# ultra_wideband.net
KiCad netlist of a schematic drawn in Altium Designer
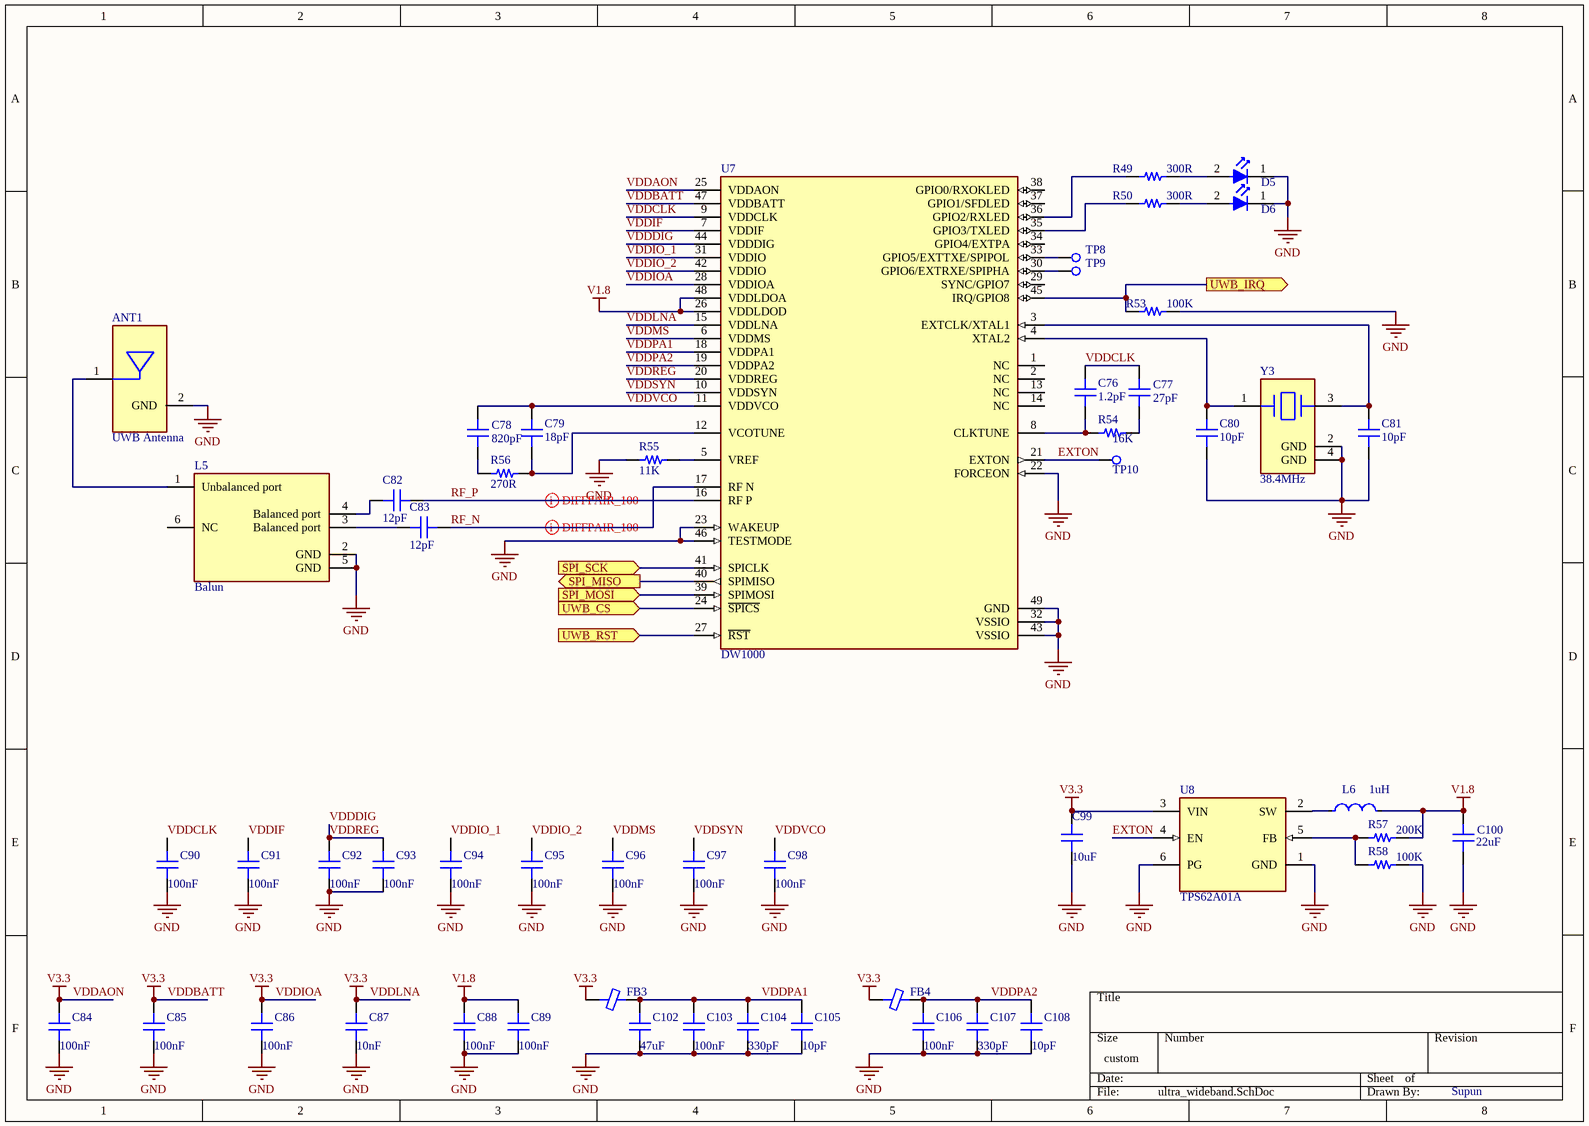
[diagram p0: ultra_wideband.SchDoc]

(export (version "E")
  (design (tool "Eeschema 10.0.6"))
  (components
    (comp (ref "ANT1")
      (value "UWB Antenna")
      (footprint "UWB_ANTENNA_1")
      (description "PCB Antenna")
      (fields (field (name "MF") "SAH"))
      (libsource (lib "Antenna") (part "UWB PCB Antenna"))
    )
    (comp (ref "C76")
      (value "1.2pF")
      (footprint "CAP 0603_1608")
      (description "SMT Capacitor")
      (fields (field (name "MF") "Murata") (field (name "MP") "GRM1885C1H1R2CA01D"))
      (libsource (lib "Capacitor") (part "Capacitor"))
    )
    (comp (ref "C77")
      (value "27pF")
      (footprint "CAP 0603_1608")
      (description "SMT Capacitor")
      (fields (field (name "MF") "Murata") (field (name "MP") "GRM1885C1H270JA01D"))
      (libsource (lib "Capacitor") (part "Capacitor"))
    )
    (comp (ref "C78")
      (value "820pF")
      (footprint "CAP 0603_1608")
      (description "SMT Capacitor")
      (fields (field (name "MF") "Murata") (field (name "MP") "GRM1885C1H821JA01D"))
      (libsource (lib "Capacitor") (part "Capacitor"))
    )
    (comp (ref "C79")
      (value "18pF")
      (footprint "CAP 0603_1608")
      (description "SMT Capacitor")
      (fields (field (name "MF") "Murata") (field (name "MP") "GRM1885C1H180JA01J"))
      (libsource (lib "Capacitor") (part "Capacitor"))
    )
    (comp (ref "C80")
      (value "10pF")
      (footprint "CAP 0603_1608")
      (description "SMT Capacitor")
      (fields (field (name "MF") "Murata") (field (name "MP") "GRM1885C1H100GA01D"))
      (libsource (lib "Capacitor") (part "Capacitor"))
    )
    (comp (ref "C81")
      (value "10pF")
      (footprint "CAP 0603_1608")
      (description "SMT Capacitor")
      (fields (field (name "MF") "Murata") (field (name "MP") "GRM1885C1H100GA01D"))
      (libsource (lib "Capacitor") (part "Capacitor"))
    )
    (comp (ref "C82")
      (value "12pF")
      (footprint "CAP 0603_1608")
      (description "SMT Capacitor")
      (fields (field (name "MF") "Murata") (field (name "MP") "GRM1885C1H120JA01J"))
      (libsource (lib "Capacitor") (part "Capacitor"))
    )
    (comp (ref "C83")
      (value "12pF")
      (footprint "CAP 0603_1608")
      (description "SMT Capacitor")
      (fields (field (name "MF") "Murata") (field (name "MP") "GRM1885C1H120JA01J"))
      (libsource (lib "Capacitor") (part "Capacitor"))
    )
    (comp (ref "C84")
      (value "100nF")
      (footprint "CAP 0603_1608")
      (description "SMT Capacitor")
      (fields (field (name "MF") "TDK") (field (name "MP") "CGA3E2X7R1E104K080AA"))
      (libsource (lib "Capacitor") (part "Capacitor"))
    )
    (comp (ref "C85")
      (value "100nF")
      (footprint "CAP 0603_1608")
      (description "SMT Capacitor")
      (fields (field (name "MF") "TDK") (field (name "MP") "CGA3E2X7R1E104K080AA"))
      (libsource (lib "Capacitor") (part "Capacitor"))
    )
    (comp (ref "C86")
      (value "100nF")
      (footprint "CAP 0603_1608")
      (description "SMT Capacitor")
      (fields (field (name "MF") "TDK") (field (name "MP") "CGA3E2X7R1E104K080AA"))
      (libsource (lib "Capacitor") (part "Capacitor"))
    )
    (comp (ref "C87")
      (value "10nF")
      (footprint "CAP 0603_1608")
      (description "SMT Capacitor")
      (fields (field (name "MF") "Murata") (field (name "MP") "GRM1885C1E103JA01D"))
      (libsource (lib "Capacitor") (part "Capacitor"))
    )
    (comp (ref "C88")
      (value "100nF")
      (footprint "CAP 0603_1608")
      (description "SMT Capacitor")
      (fields (field (name "MF") "TDK") (field (name "MP") "CGA3E2X7R1E104K080AA"))
      (libsource (lib "Capacitor") (part "Capacitor"))
    )
    (comp (ref "C89")
      (value "100nF")
      (footprint "CAP 0603_1608")
      (description "SMT Capacitor")
      (fields (field (name "MF") "TDK") (field (name "MP") "CGA3E2X7R1E104K080AA"))
      (libsource (lib "Capacitor") (part "Capacitor"))
    )
    (comp (ref "C90")
      (value "100nF")
      (footprint "CAP 0603_1608")
      (description "SMT Capacitor")
      (fields (field (name "MF") "TDK") (field (name "MP") "CGA3E2X7R1E104K080AA"))
      (libsource (lib "Capacitor") (part "Capacitor"))
    )
    (comp (ref "C91")
      (value "100nF")
      (footprint "CAP 0603_1608")
      (description "SMT Capacitor")
      (fields (field (name "MF") "TDK") (field (name "MP") "CGA3E2X7R1E104K080AA"))
      (libsource (lib "Capacitor") (part "Capacitor"))
    )
    (comp (ref "C92")
      (value "100nF")
      (footprint "CAP 0603_1608")
      (description "SMT Capacitor")
      (fields (field (name "MF") "TDK") (field (name "MP") "CGA3E2X7R1E104K080AA"))
      (libsource (lib "Capacitor") (part "Capacitor"))
    )
    (comp (ref "C93")
      (value "100nF")
      (footprint "CAP 0603_1608")
      (description "SMT Capacitor")
      (fields (field (name "MF") "TDK") (field (name "MP") "CGA3E2X7R1E104K080AA"))
      (libsource (lib "Capacitor") (part "Capacitor"))
    )
    (comp (ref "C94")
      (value "100nF")
      (footprint "CAP 0603_1608")
      (description "SMT Capacitor")
      (fields (field (name "MF") "TDK") (field (name "MP") "CGA3E2X7R1E104K080AA"))
      (libsource (lib "Capacitor") (part "Capacitor"))
    )
    (comp (ref "C95")
      (value "100nF")
      (footprint "CAP 0603_1608")
      (description "SMT Capacitor")
      (fields (field (name "MF") "TDK") (field (name "MP") "CGA3E2X7R1E104K080AA"))
      (libsource (lib "Capacitor") (part "Capacitor"))
    )
    (comp (ref "C96")
      (value "100nF")
      (footprint "CAP 0603_1608")
      (description "SMT Capacitor")
      (fields (field (name "MF") "TDK") (field (name "MP") "CGA3E2X7R1E104K080AA"))
      (libsource (lib "Capacitor") (part "Capacitor"))
    )
    (comp (ref "C97")
      (value "100nF")
      (footprint "CAP 0603_1608")
      (description "SMT Capacitor")
      (fields (field (name "MF") "TDK") (field (name "MP") "CGA3E2X7R1E104K080AA"))
      (libsource (lib "Capacitor") (part "Capacitor"))
    )
    (comp (ref "C98")
      (value "100nF")
      (footprint "CAP 0603_1608")
      (description "SMT Capacitor")
      (fields (field (name "MF") "TDK") (field (name "MP") "CGA3E2X7R1E104K080AA"))
      (libsource (lib "Capacitor") (part "Capacitor"))
    )
    (comp (ref "C99")
      (value "10uF")
      (footprint "CAP 0603_1608")
      (description "SMT Capacitor")
      (fields (field (name "MF") "Murata") (field (name "MP") "GRM188R61C106MAALD"))
      (libsource (lib "Capacitor") (part "Capacitor"))
    )
    (comp (ref "C100")
      (value "22uF")
      (footprint "CAP 0603_1608")
      (description "SMT Capacitor")
      (fields (field (name "MF") "Murata") (field (name "MP") "GRM188R61A226ME15D"))
      (libsource (lib "Capacitor") (part "Capacitor"))
    )
    (comp (ref "C102")
      (value "47uF")
      (footprint "CAP 0603_1608")
      (description "SMT Capacitor")
      (fields (field (name "MF") "Murata") (field (name "MP") "GRM188R60J476ME15D"))
      (libsource (lib "Capacitor") (part "Capacitor"))
    )
    (comp (ref "C103")
      (value "100nF")
      (footprint "CAP 0603_1608")
      (description "SMT Capacitor")
      (fields (field (name "MF") "TDK") (field (name "MP") "CGA3E2X7R1E104K080AA"))
      (libsource (lib "Capacitor") (part "Capacitor"))
    )
    (comp (ref "C104")
      (value "330pF")
      (footprint "CAP 0603_1608")
      (description "SMT Capacitor")
      (fields (field (name "MF") "Murata") (field (name "MP") "GRM1885C1H331JA01D"))
      (libsource (lib "Capacitor") (part "Capacitor"))
    )
    (comp (ref "C105")
      (value "10pF")
      (footprint "CAP 0603_1608")
      (description "SMT Capacitor")
      (fields (field (name "MF") "Murata") (field (name "MP") "GRM1885C1H100GA01D"))
      (libsource (lib "Capacitor") (part "Capacitor"))
    )
    (comp (ref "C106")
      (value "100nF")
      (footprint "CAP 0603_1608")
      (description "SMT Capacitor")
      (fields (field (name "MF") "TDK") (field (name "MP") "CGA3E2X7R1E104K080AA"))
      (libsource (lib "Capacitor") (part "Capacitor"))
    )
    (comp (ref "C107")
      (value "330pF")
      (footprint "CAP 0603_1608")
      (description "SMT Capacitor")
      (fields (field (name "MF") "Murata") (field (name "MP") "GRM1885C1H331JA01D"))
      (libsource (lib "Capacitor") (part "Capacitor"))
    )
    (comp (ref "C108")
      (value "10pF")
      (footprint "CAP 0603_1608")
      (description "SMT Capacitor")
      (fields (field (name "MF") "Murata") (field (name "MP") "GRM1885C1H100GA01D"))
      (libsource (lib "Capacitor") (part "Capacitor"))
    )
    (comp (ref "D5")
      (value "Green")
      (footprint "Würth_Elektronik_0_MFG")
      (description "Led Diffused SMD")
      (fields (field (name "MF") "LiteOn") (field (name "MP") "LTST-C190KGKT"))
      (libsource (lib "Diode") (part "LED SMD"))
    )
    (comp (ref "D6")
      (value "Red")
      (footprint "Würth_Elektronik_0_MFG")
      (description "Led Diffused SMD")
      (fields (field (name "MF") "LiteOn") (field (name "MP") "LTST-C190KRKT"))
      (libsource (lib "Diode") (part "LED SMD"))
    )
    (comp (ref "FB3")
      (value "Ferrite Beads")
      (footprint "Murata_BLM18-0_15-t0_8_MFG")
      (description "SMT Ferrite Chip")
      (fields (field (name "MF") "Murata") (field (name "MP") "BLM18AG601SH1D"))
      (libsource (lib "Passive") (part "Ferrite Chip"))
    )
    (comp (ref "FB4")
      (value "Ferrite Beads")
      (footprint "Murata_BLM18-0_15-t0_8_MFG")
      (description "SMT Ferrite Chip")
      (fields (field (name "MF") "Murata") (field (name "MP") "BLM18AG601SH1D"))
      (libsource (lib "Passive") (part "Ferrite Chip"))
    )
    (comp (ref "L5")
      (value "Balun")
      (footprint "TDK_HHM1595A1_MFG")
      (description "Signal Conditioning LTCC BALUN 3000-8000MHz")
      (fields (field (name "MF") "TDK") (field (name "MP") "HHM1595A1"))
      (libsource (lib "Antenna") (part "HHM1595A1"))
    )
    (comp (ref "L6")
      (value "1uH")
      (footprint "IND 1008_2520")
      (description "Fixed Inductors 2.2uH 20% High Temp AEC-Q200")
      (fields (field (name "MF") "Murata") (field (name "MP") "DFE252012F-1R0M=P2"))
      (libsource (lib "Inductor") (part "Inductor_sm"))
    )
    (comp (ref "R49")
      (value "300R")
      (footprint "RES 0603_1608")
      (description "SMT Resistor")
      (fields (field (name "MF") "YAGEO") (field (name "MP") "AC0603FR-07300RL"))
      (libsource (lib "Resistor") (part "Resistor"))
    )
    (comp (ref "R50")
      (value "300R")
      (footprint "RES 0603_1608")
      (description "SMT Resistor")
      (fields (field (name "MF") "YAGEO") (field (name "MP") "AC0603FR-07300RL"))
      (libsource (lib "Resistor") (part "Resistor"))
    )
    (comp (ref "R53")
      (value "100K")
      (footprint "RES 0603_1608")
      (description "SMT Resistor")
      (fields (field (name "MF") "YAGEO") (field (name "MP") "AC0603FR-07100KL"))
      (libsource (lib "Resistor") (part "Resistor"))
    )
    (comp (ref "R54")
      (value "16K")
      (footprint "RES 0603_1608")
      (description "SMT Resistor")
      (fields (field (name "MF") "YAGEO") (field (name "MP") "AC0603FR-0716KL"))
      (libsource (lib "Resistor") (part "Resistor"))
    )
    (comp (ref "R55")
      (value "11K")
      (footprint "RES 0603_1608")
      (description "SMT Resistor")
      (fields (field (name "MF") "YAGEO") (field (name "MP") "AC0603FR-0711KL"))
      (libsource (lib "Resistor") (part "Resistor"))
    )
    (comp (ref "R56")
      (value "270R")
      (footprint "RES 0603_1608")
      (description "SMT Resistor")
      (fields (field (name "MF") "YAGEO") (field (name "MP") "AC0603FR-07270RL"))
      (libsource (lib "Resistor") (part "Resistor"))
    )
    (comp (ref "R57")
      (value "200K")
      (footprint "RES 0603_1608")
      (description "SMT Resistor")
      (fields (field (name "MF") "YAGEO") (field (name "MP") "AC0603FR-07200KL"))
      (libsource (lib "Resistor") (part "Resistor"))
    )
    (comp (ref "R58")
      (value "100K")
      (footprint "RES 0603_1608")
      (description "SMT Resistor")
      (fields (field (name "MF") "YAGEO") (field (name "MP") "AC0603FR-07100KL"))
      (libsource (lib "Resistor") (part "Resistor"))
    )
    (comp (ref "TP8")
      (value "Test Point")
      (footprint "TPSMD_S1")
      (libsource (lib "Passive") (part "Test Point"))
    )
    (comp (ref "TP9")
      (value "Test Point")
      (footprint "TPSMD_S1")
      (libsource (lib "Passive") (part "Test Point"))
    )
    (comp (ref "TP10")
      (value "Test Point")
      (footprint "TPSMD_S1")
      (libsource (lib "Passive") (part "Test Point"))
    )
    (comp (ref "U7")
      (value "DW1000")
      (footprint "Qorvo_1_IPC_B")
      (fields (field (name "MF") "Qorvo") (field (name "MP") "DW1000-I-TR13"))
      (libsource (lib "UltraWideBand") (part "DW1000"))
    )
    (comp (ref "U8")
      (value "TPS62A01A")
      (footprint "TI SOT-563 DRL")
      (fields (field (name "MF") "Texas Instruments") (field (name "MP") "TPS62A01ADRLR"))
      (libsource (lib "SwitchingRegulators") (part "TPS62A01A"))
    )
    (comp (ref "Y3")
      (value "38.4MHz")
      (footprint "ABRACON ABM8G")
      (description "Crystals AEC-Q200 CRYSTAL 4pin SMD")
      (fields (field (name "MF") "ECS") (field (name "MP") "ECS-384-10-33B-CKY-TR"))
      (libsource (lib "Crystal") (part "Crystal"))
    )
  )
  (nets
    (net (code "1") (name "/EXTON") (class "Default")
      (node (ref "TP10") (pin "1") (pinfunction "TP_1") (pintype "passive"))
      (node (ref "U7") (pin "21") (pinfunction "EXTON_21") (pintype "output"))
      (node (ref "U8") (pin "4") (pinfunction "EN_4") (pintype "input"))
    )
    (net (code "2") (name "/RF_N") (class "Default")
      (node (ref "C83") (pin "1") (pinfunction "1_1") (pintype "passive"))
      (node (ref "U7") (pin "17") (pinfunction "RF_N_17") (pintype "passive"))
    )
    (net (code "3") (name "/RF_P") (class "Default")
      (node (ref "C82") (pin "1") (pinfunction "1_1") (pintype "passive"))
      (node (ref "U7") (pin "16") (pinfunction "RF_P_16") (pintype "passive"))
    )
    (net (code "4") (name "/SPI_MISO") (class "Default")
      (node (ref "U7") (pin "40") (pinfunction "SPIMISO_40") (pintype "output"))
    )
    (net (code "5") (name "/SPI_MOSI") (class "Default")
      (node (ref "U7") (pin "39") (pinfunction "SPIMOSI_39") (pintype "input"))
    )
    (net (code "6") (name "/SPI_SCK") (class "Default")
      (node (ref "U7") (pin "41") (pinfunction "SPICLK_41") (pintype "input"))
    )
    (net (code "7") (name "/UWB_CS") (class "Default")
      (node (ref "U7") (pin "24") (pinfunction "~{SPICS}_24") (pintype "input"))
    )
    (net (code "8") (name "/UWB_IRQ") (class "Default")
      (node (ref "R53") (pin "2") (pinfunction "2_2") (pintype "passive"))
      (node (ref "U7") (pin "45") (pinfunction "IRQ/GPIO8_45") (pintype "bidirectional"))
    )
    (net (code "9") (name "/UWB_RST") (class "Default")
      (node (ref "U7") (pin "27") (pinfunction "~{RST}_27") (pintype "input"))
    )
    (net (code "10") (name "/VDDCLK") (class "Default")
      (node (ref "C76") (pin "2") (pinfunction "2_2") (pintype "passive"))
      (node (ref "C77") (pin "2") (pinfunction "2_2") (pintype "passive"))
      (node (ref "C90") (pin "1") (pinfunction "1_1") (pintype "passive"))
      (node (ref "U7") (pin "9") (pinfunction "VDDCLK_9") (pintype "power_in"))
    )
    (net (code "11") (name "/VDDDIG") (class "Default")
      (node (ref "C92") (pin "1") (pinfunction "1_1") (pintype "passive"))
      (node (ref "C93") (pin "1") (pinfunction "1_1") (pintype "passive"))
      (node (ref "U7") (pin "20") (pinfunction "VDDREG_20") (pintype "power_in"))
      (node (ref "U7") (pin "44") (pinfunction "VDDDIG_44") (pintype "power_in"))
    )
    (net (code "12") (name "/VDDIF") (class "Default")
      (node (ref "C91") (pin "1") (pinfunction "1_1") (pintype "passive"))
      (node (ref "U7") (pin "7") (pinfunction "VDDIF_7") (pintype "power_in"))
    )
    (net (code "13") (name "/VDDIO_1") (class "Default")
      (node (ref "C94") (pin "1") (pinfunction "1_1") (pintype "passive"))
      (node (ref "U7") (pin "31") (pinfunction "VDDIO_31") (pintype "power_in"))
    )
    (net (code "14") (name "/VDDIO_2") (class "Default")
      (node (ref "C95") (pin "1") (pinfunction "1_1") (pintype "passive"))
      (node (ref "U7") (pin "42") (pinfunction "VDDIO_42") (pintype "power_in"))
    )
    (net (code "15") (name "/VDDMS") (class "Default")
      (node (ref "C96") (pin "1") (pinfunction "1_1") (pintype "passive"))
      (node (ref "U7") (pin "6") (pinfunction "VDDMS_6") (pintype "power_in"))
    )
    (net (code "16") (name "/VDDPA1") (class "Default")
      (node (ref "C102") (pin "2") (pinfunction "2_2") (pintype "passive"))
      (node (ref "C103") (pin "1") (pinfunction "1_1") (pintype "passive"))
      (node (ref "C104") (pin "2") (pinfunction "2_2") (pintype "passive"))
      (node (ref "C105") (pin "2") (pinfunction "2_2") (pintype "passive"))
      (node (ref "FB3") (pin "2") (pinfunction "2_2") (pintype "passive"))
      (node (ref "U7") (pin "18") (pinfunction "VDDPA1_18") (pintype "power_in"))
    )
    (net (code "17") (name "/VDDPA2") (class "Default")
      (node (ref "C106") (pin "1") (pinfunction "1_1") (pintype "passive"))
      (node (ref "C107") (pin "2") (pinfunction "2_2") (pintype "passive"))
      (node (ref "C108") (pin "2") (pinfunction "2_2") (pintype "passive"))
      (node (ref "FB4") (pin "2") (pinfunction "2_2") (pintype "passive"))
      (node (ref "U7") (pin "19") (pinfunction "VDDPA2_19") (pintype "power_in"))
    )
    (net (code "18") (name "/VDDSYN") (class "Default")
      (node (ref "C97") (pin "1") (pinfunction "1_1") (pintype "passive"))
      (node (ref "U7") (pin "10") (pinfunction "VDDSYN_10") (pintype "power_in"))
    )
    (net (code "19") (name "/VDDVCO") (class "Default")
      (node (ref "C78") (pin "2") (pinfunction "2_2") (pintype "passive"))
      (node (ref "C79") (pin "2") (pinfunction "2_2") (pintype "passive"))
      (node (ref "C98") (pin "1") (pinfunction "1_1") (pintype "passive"))
      (node (ref "U7") (pin "11") (pinfunction "VDDVCO_11") (pintype "power_in"))
    )
    (net (code "20") (name "GND") (class "Default")
      (node (ref "ANT1") (pin "2") (pinfunction "GND_2") (pintype "passive"))
      (node (ref "C100") (pin "2") (pinfunction "2_2") (pintype "passive"))
      (node (ref "C102") (pin "1") (pinfunction "1_1") (pintype "passive"))
      (node (ref "C103") (pin "2") (pinfunction "2_2") (pintype "passive"))
      (node (ref "C104") (pin "1") (pinfunction "1_1") (pintype "passive"))
      (node (ref "C105") (pin "1") (pinfunction "1_1") (pintype "passive"))
      (node (ref "C106") (pin "2") (pinfunction "2_2") (pintype "passive"))
      (node (ref "C107") (pin "1") (pinfunction "1_1") (pintype "passive"))
      (node (ref "C108") (pin "1") (pinfunction "1_1") (pintype "passive"))
      (node (ref "C80") (pin "1") (pinfunction "1_1") (pintype "passive"))
      (node (ref "C81") (pin "1") (pinfunction "1_1") (pintype "passive"))
      (node (ref "C84") (pin "2") (pinfunction "2_2") (pintype "passive"))
      (node (ref "C85") (pin "2") (pinfunction "2_2") (pintype "passive"))
      (node (ref "C86") (pin "2") (pinfunction "2_2") (pintype "passive"))
      (node (ref "C87") (pin "2") (pinfunction "2_2") (pintype "passive"))
      (node (ref "C88") (pin "2") (pinfunction "2_2") (pintype "passive"))
      (node (ref "C89") (pin "2") (pinfunction "2_2") (pintype "passive"))
      (node (ref "C90") (pin "2") (pinfunction "2_2") (pintype "passive"))
      (node (ref "C91") (pin "2") (pinfunction "2_2") (pintype "passive"))
      (node (ref "C92") (pin "2") (pinfunction "2_2") (pintype "passive"))
      (node (ref "C93") (pin "2") (pinfunction "2_2") (pintype "passive"))
      (node (ref "C94") (pin "2") (pinfunction "2_2") (pintype "passive"))
      (node (ref "C95") (pin "2") (pinfunction "2_2") (pintype "passive"))
      (node (ref "C96") (pin "2") (pinfunction "2_2") (pintype "passive"))
      (node (ref "C97") (pin "2") (pinfunction "2_2") (pintype "passive"))
      (node (ref "C98") (pin "2") (pinfunction "2_2") (pintype "passive"))
      (node (ref "C99") (pin "2") (pinfunction "2_2") (pintype "passive"))
      (node (ref "D5") (pin "1") (pinfunction "C_1") (pintype "passive"))
      (node (ref "D6") (pin "1") (pinfunction "C_1") (pintype "passive"))
      (node (ref "L5") (pin "2") (pinfunction "GND_2") (pintype "power_in"))
      (node (ref "L5") (pin "5") (pinfunction "GND_5") (pintype "power_in"))
      (node (ref "R53") (pin "1") (pinfunction "1_1") (pintype "passive"))
      (node (ref "R55") (pin "1") (pinfunction "1_1") (pintype "passive"))
      (node (ref "R58") (pin "2") (pinfunction "2_2") (pintype "passive"))
      (node (ref "U7") (pin "22") (pinfunction "FORCEON_22") (pintype "input"))
      (node (ref "U7") (pin "23") (pinfunction "WAKEUP_23") (pintype "input"))
      (node (ref "U7") (pin "32") (pinfunction "VSSIO_32") (pintype "power_in"))
      (node (ref "U7") (pin "43") (pinfunction "VSSIO_43") (pintype "power_in"))
      (node (ref "U7") (pin "46") (pinfunction "TESTMODE_46") (pintype "input"))
      (node (ref "U7") (pin "49") (pinfunction "GND_49") (pintype "power_in"))
      (node (ref "U8") (pin "1") (pinfunction "GND_1") (pintype "power_in"))
      (node (ref "U8") (pin "6") (pinfunction "PG_6") (pintype "passive"))
      (node (ref "Y3") (pin "2") (pinfunction "GND_2") (pintype "power_in"))
      (node (ref "Y3") (pin "4") (pinfunction "GND_4") (pintype "power_in"))
    )
    (net (code "21") (name "Net-(C77-Pad1)") (class "Default")
      (node (ref "C77") (pin "1") (pinfunction "1_1") (pintype "passive"))
      (node (ref "R54") (pin "1") (pinfunction "1_1") (pintype "passive"))
    )
    (net (code "22") (name "Net-(C78-Pad1)") (class "Default")
      (node (ref "C78") (pin "1") (pinfunction "1_1") (pintype "passive"))
      (node (ref "R56") (pin "2") (pinfunction "2_2") (pintype "passive"))
    )
    (net (code "23") (name "Net-(C82-Pad2)") (class "Default")
      (node (ref "C82") (pin "2") (pinfunction "2_2") (pintype "passive"))
      (node (ref "L5") (pin "4") (pinfunction "Balanced_port_4") (pintype "passive"))
    )
    (net (code "24") (name "Net-(C83-Pad2)") (class "Default")
      (node (ref "C83") (pin "2") (pinfunction "2_2") (pintype "passive"))
      (node (ref "L5") (pin "3") (pinfunction "Balanced_port_3") (pintype "passive"))
    )
    (net (code "25") (name "Net-(D5-A)") (class "Default")
      (node (ref "D5") (pin "2") (pinfunction "A_2") (pintype "passive"))
      (node (ref "R49") (pin "2") (pinfunction "2_2") (pintype "passive"))
    )
    (net (code "26") (name "Net-(D6-A)") (class "Default")
      (node (ref "D6") (pin "2") (pinfunction "A_2") (pintype "passive"))
      (node (ref "R50") (pin "2") (pinfunction "2_2") (pintype "passive"))
    )
    (net (code "27") (name "Net-(L5-Unbalanced_port)") (class "Default")
      (node (ref "ANT1") (pin "1") (pinfunction "1_1") (pintype "passive"))
      (node (ref "L5") (pin "1") (pinfunction "Unbalanced_port_1") (pintype "passive"))
    )
    (net (code "28") (name "Net-(TP8-TP)") (class "Default")
      (node (ref "TP8") (pin "1") (pinfunction "TP_1") (pintype "passive"))
      (node (ref "U7") (pin "33") (pinfunction "GPIO5/EXTTXE/SPIPOL_33") (pintype "bidirectional"))
    )
    (net (code "29") (name "Net-(TP9-TP)") (class "Default")
      (node (ref "TP9") (pin "1") (pinfunction "TP_1") (pintype "passive"))
      (node (ref "U7") (pin "30") (pinfunction "GPIO6/EXTRXE/SPIPHA_30") (pintype "bidirectional"))
    )
    (net (code "30") (name "Net-(U7-CLKTUNE)") (class "Default")
      (node (ref "C76") (pin "1") (pinfunction "1_1") (pintype "passive"))
      (node (ref "R54") (pin "2") (pinfunction "2_2") (pintype "passive"))
      (node (ref "U7") (pin "8") (pinfunction "CLKTUNE_8") (pintype "passive"))
    )
    (net (code "31") (name "Net-(U7-EXTCLK{slash}XTAL1)") (class "Default")
      (node (ref "C81") (pin "2") (pinfunction "2_2") (pintype "passive"))
      (node (ref "U7") (pin "3") (pinfunction "EXTCLK/XTAL1_3") (pintype "input"))
      (node (ref "Y3") (pin "3") (pinfunction "3_3") (pintype "passive"))
    )
    (net (code "32") (name "Net-(U7-GPIO2{slash}RXLED)") (class "Default")
      (node (ref "R49") (pin "1") (pinfunction "1_1") (pintype "passive"))
      (node (ref "U7") (pin "36") (pinfunction "GPIO2/RXLED_36") (pintype "bidirectional"))
    )
    (net (code "33") (name "Net-(U7-GPIO3{slash}TXLED)") (class "Default")
      (node (ref "R50") (pin "1") (pinfunction "1_1") (pintype "passive"))
      (node (ref "U7") (pin "35") (pinfunction "GPIO3/TXLED_35") (pintype "bidirectional"))
    )
    (net (code "34") (name "Net-(U7-VCOTUNE)") (class "Default")
      (node (ref "C79") (pin "1") (pinfunction "1_1") (pintype "passive"))
      (node (ref "R56") (pin "1") (pinfunction "1_1") (pintype "passive"))
      (node (ref "U7") (pin "12") (pinfunction "VCOTUNE_12") (pintype "power_in"))
    )
    (net (code "35") (name "Net-(U7-VREF)") (class "Default")
      (node (ref "R55") (pin "2") (pinfunction "2_2") (pintype "passive"))
      (node (ref "U7") (pin "5") (pinfunction "VREF_5") (pintype "passive"))
    )
    (net (code "36") (name "Net-(U7-XTAL2)") (class "Default")
      (node (ref "C80") (pin "2") (pinfunction "2_2") (pintype "passive"))
      (node (ref "U7") (pin "4") (pinfunction "XTAL2_4") (pintype "input"))
      (node (ref "Y3") (pin "1") (pinfunction "1_1") (pintype "passive"))
    )
    (net (code "37") (name "Net-(U8-FB)") (class "Default")
      (node (ref "R57") (pin "1") (pinfunction "1_1") (pintype "passive"))
      (node (ref "R58") (pin "1") (pinfunction "1_1") (pintype "passive"))
      (node (ref "U8") (pin "5") (pinfunction "FB_5") (pintype "input"))
    )
    (net (code "38") (name "Net-(U8-SW)") (class "Default")
      (node (ref "L6") (pin "1") (pinfunction "1_1") (pintype "passive"))
      (node (ref "U8") (pin "2") (pinfunction "SW_2") (pintype "power_in"))
    )
    (net (code "39") (name "V1.8") (class "Default")
      (node (ref "C100") (pin "1") (pinfunction "1_1") (pintype "passive"))
      (node (ref "C88") (pin "1") (pinfunction "1_1") (pintype "passive"))
      (node (ref "C89") (pin "1") (pinfunction "1_1") (pintype "passive"))
      (node (ref "L6") (pin "2") (pinfunction "2_2") (pintype "passive"))
      (node (ref "R57") (pin "2") (pinfunction "2_2") (pintype "passive"))
      (node (ref "U7") (pin "26") (pinfunction "VDDLDOD_26") (pintype "power_in"))
      (node (ref "U7") (pin "48") (pinfunction "VDDLDOA_48") (pintype "power_in"))
    )
    (net (code "40") (name "V3.3") (class "Default")
      (node (ref "C84") (pin "1") (pinfunction "1_1") (pintype "passive"))
      (node (ref "C85") (pin "1") (pinfunction "1_1") (pintype "passive"))
      (node (ref "C86") (pin "1") (pinfunction "1_1") (pintype "passive"))
      (node (ref "C87") (pin "1") (pinfunction "1_1") (pintype "passive"))
      (node (ref "C99") (pin "1") (pinfunction "1_1") (pintype "passive"))
      (node (ref "FB3") (pin "1") (pinfunction "1_1") (pintype "passive"))
      (node (ref "FB4") (pin "1") (pinfunction "1_1") (pintype "passive"))
      (node (ref "U7") (pin "15") (pinfunction "VDDLNA_15") (pintype "power_in"))
      (node (ref "U7") (pin "25") (pinfunction "VDDAON_25") (pintype "power_in"))
      (node (ref "U7") (pin "28") (pinfunction "VDDIOA_28") (pintype "power_in"))
      (node (ref "U7") (pin "47") (pinfunction "VDDBATT_47") (pintype "power_in"))
      (node (ref "U8") (pin "3") (pinfunction "VIN_3") (pintype "power_in"))
    )
    (net (code "41") (name "unconnected-(L5-NC-Pad6)") (class "Default")
      (node (ref "L5") (pin "6") (pinfunction "NC_6") (pintype "passive"))
    )
    (net (code "42") (name "unconnected-(U7-GPIO0{slash}RXOKLED-Pad38)") (class "Default")
      (node (ref "U7") (pin "38") (pinfunction "GPIO0/RXOKLED_38") (pintype "bidirectional"))
    )
    (net (code "43") (name "unconnected-(U7-GPIO1{slash}SFDLED-Pad37)") (class "Default")
      (node (ref "U7") (pin "37") (pinfunction "GPIO1/SFDLED_37") (pintype "bidirectional"))
    )
    (net (code "44") (name "unconnected-(U7-GPIO4{slash}EXTPA-Pad34)") (class "Default")
      (node (ref "U7") (pin "34") (pinfunction "GPIO4/EXTPA_34") (pintype "bidirectional"))
    )
    (net (code "45") (name "unconnected-(U7-NC-Pad1)") (class "Default")
      (node (ref "U7") (pin "1") (pinfunction "NC_1") (pintype "passive"))
    )
    (net (code "46") (name "unconnected-(U7-NC-Pad2)") (class "Default")
      (node (ref "U7") (pin "2") (pinfunction "NC_2") (pintype "passive"))
    )
    (net (code "47") (name "unconnected-(U7-NC-Pad13)") (class "Default")
      (node (ref "U7") (pin "13") (pinfunction "NC_13") (pintype "passive"))
    )
    (net (code "48") (name "unconnected-(U7-NC-Pad14)") (class "Default")
      (node (ref "U7") (pin "14") (pinfunction "NC_14") (pintype "passive"))
    )
    (net (code "49") (name "unconnected-(U7-SYNC{slash}GPIO7-Pad29)") (class "Default")
      (node (ref "U7") (pin "29") (pinfunction "SYNC/GPIO7_29") (pintype "bidirectional"))
    )
  )
)
